# BSPDTester.net
KiCad netlist of a schematic drawn in Altium Designer
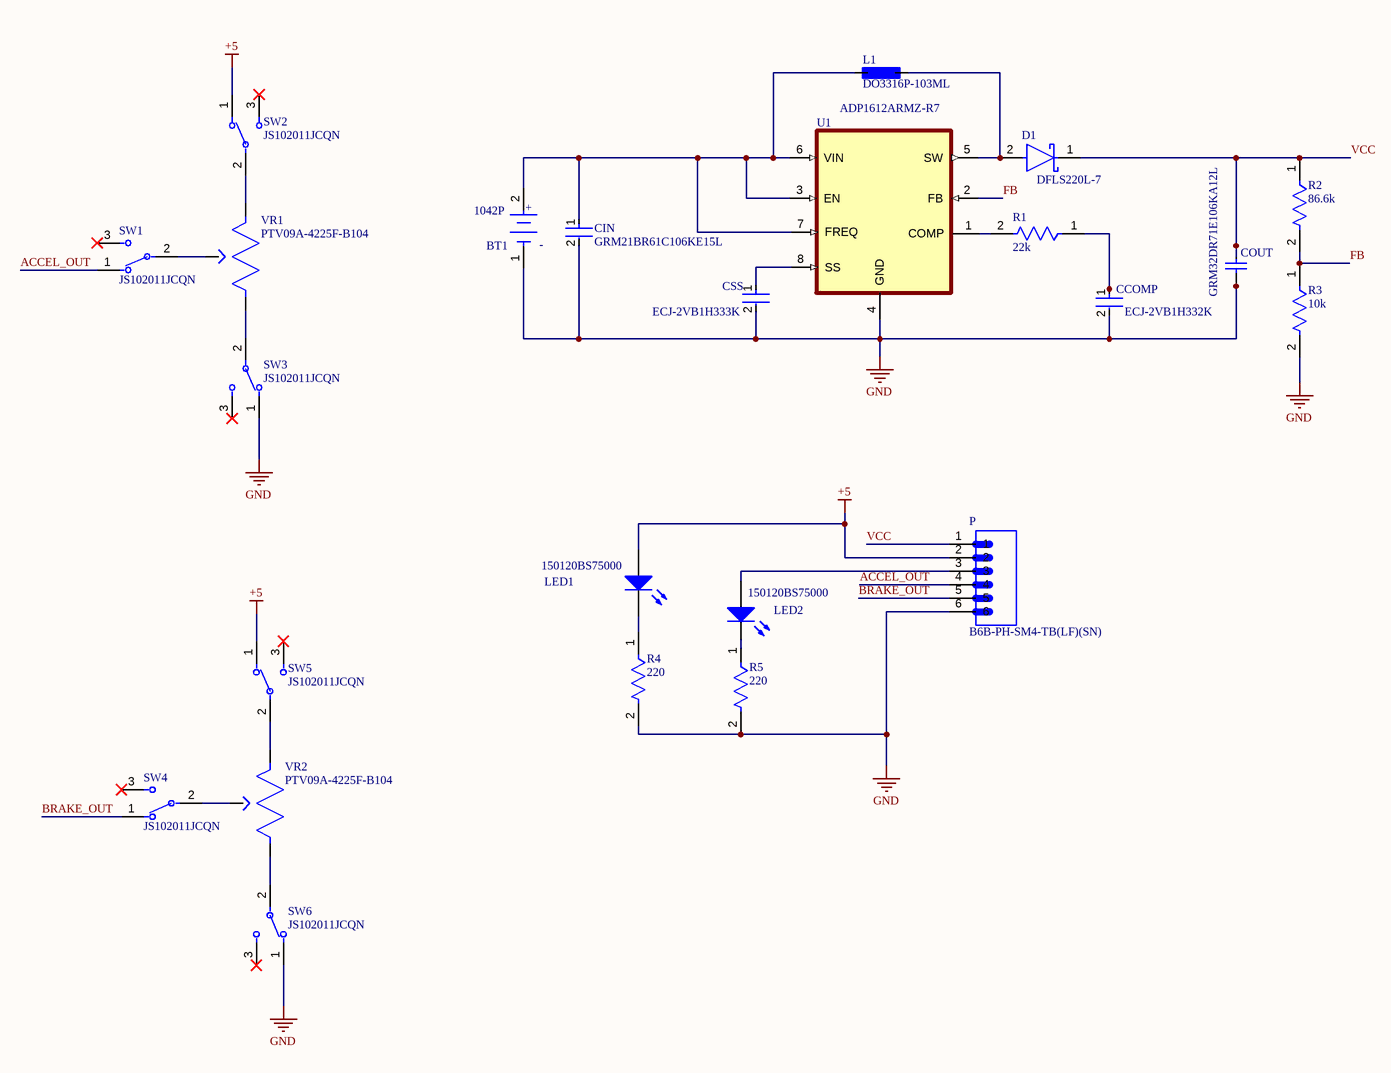
[diagram p0: BSPDTester.SchDoc]

(export (version "E")
  (design (tool "Eeschema 10.0.6"))
  (components
    (comp (ref "BT1")
      (value "1042P")
      (footprint "FP-1042P-MFG")
      (description "BATTERY HOLDER 18650 SMD TAB")
      (libsource (lib "Altium Content Vault") (part "60d3b5b901a8747834971d0eb8cf3fd"))
    )
    (comp (ref "CCOMP")
      (value "ECJ-2VB1H332K")
      (footprint "FP-C0805C-DG-MFG")
      (description "CAP CER 10UF 10V X5R 0805")
      (fields (field (name "TOLERANCE") "10%") (field (name "MANUFACTURER PART NUMBER") "C0805C106K8PACTU"))
      (libsource (lib "Altium Content Vault") (part "11868f565c42a9108669ba33697ecf6"))
    )
    (comp (ref "CIN")
      (value "GRM21BR61C106KE15L")
      (footprint "FP-GRM21B-0_1-IPC_C")
      (description "Chip Multilayer Ceramic Capacitors for General Purpose, 0805, 10uF, X5R, 15%, 10%, 16V")
      (fields (field (name "TOLERANCE") "10%") (field (name "VOLTAGE") "16V"))
      (libsource (lib "Altium Content Vault") (part "b4654b650e69147ec39a6b967a45e02"))
    )
    (comp (ref "COUT")
      (value "GRM32DR71E106KA12L")
      (footprint "CAPC3225X220X30LL30")
      (description "Chip Capacitor, 10 uF, +/- 10%, 25 V, -55 to 125 degC, 1210 (3225 Metric), RoHS, Tape and Reel")
      (fields (field (name "MANUFACTURER") "Murata"))
      (libsource (lib "Altium Content Vault") (part "CAP-NP-2"))
    )
    (comp (ref "CSS")
      (value "ECJ-2VB1H333K")
      (footprint "FP-C0805C-DG-MFG")
      (description "CAP CER 10UF 10V X5R 0805")
      (fields (field (name "TOLERANCE") "10%") (field (name "MANUFACTURER PART NUMBER") "C0805C106K8PACTU"))
      (libsource (lib "Altium Content Vault") (part "11868f565c42a9108669ba33697ecf6"))
    )
    (comp (ref "D1")
      (value "DFLS220L-7")
      (footprint "FP-PowerDI123-MFG")
      (description "DIODE SCHOTTKY 20V 2A POWERDI123")
      (fields
        (field (name "MANUFACTURER") "Diodes Inc.")
        (field (name "OCTOPART") "https://octopart.com/dfls220l-7-diodes+inc.-328575")
      )
      (libsource (lib "Altium Content Vault") (part "1d6ec82d83fb6aee721767c19dac4b9"))
    )
    (comp (ref "L1")
      (value "DO3316P-103ML")
      (footprint "DO3316P")
      (description "<b>COILCRAFT</b>")
      (fields (field (name "MP") "DO3316P") (field (name "MF") "Coilcraft"))
      (libsource (lib "DO3316P") (part "DO3316P"))
    )
    (comp (ref "LED1")
      (value "150120BS75000")
      (footprint "1206_A")
      (description "SMD mono-color Chip LED, WL-SMCW, Blue")
      (fields (field (name "MANUFACTURER") "Wuerth Elektronik"))
      (libsource (lib "Altium Content Vault") (part "WE-LED_K1A2-2"))
    )
    (comp (ref "LED2")
      (value "150120BS75000")
      (footprint "1206_A")
      (description "SMD mono-color Chip LED, WL-SMCW, Blue")
      (fields (field (name "MANUFACTURER") "Wuerth Elektronik"))
      (libsource (lib "Altium Content Vault") (part "WE-LED_K1A2-2"))
    )
    (comp (ref "P")
      (value "B6B-PH-SM4-TB(LF)(SN)")
      (footprint "JST_B6B-PH-SM4-TB(LF)(SN)")
      (description "Connector Header Surface Mount 6 position 0.079 _2.00mm_")
      (fields (field (name "MF") "JST Sales") (field (name "MP") "B6B-PH-SM4-TB_LF__SN_"))
      (libsource (lib "B6B-PH-SM4-TB_LF__SN_") (part "B6B-PH-SM4-TB(LF)(SN)"))
    )
    (comp (ref "R1")
      (value "22k")
      (footprint "FP-CRCW1206-e3-IPC_A")
      (description "RES Thick Film, 22kΩ, 1%, 0.25W, 100ppm/°C, 1206")
      (fields (field (name "TOLERANCE") "1%"))
      (libsource (lib "Altium Content Vault") (part "1029c3af85768c4190bb7ad29bc67b5"))
    )
    (comp (ref "R2")
      (value "86.6k")
      (footprint "FP-CRCW1206-e3-IPC_A")
      (description "RES Thick Film, 22kΩ, 1%, 0.25W, 100ppm/°C, 1206")
      (fields (field (name "TOLERANCE") "1%"))
      (libsource (lib "Altium Content Vault") (part "1029c3af85768c4190bb7ad29bc67b5"))
    )
    (comp (ref "R3")
      (value "10k")
      (footprint "FP-CRCW1206-e3-IPC_A")
      (description "RES Thick Film, 22kΩ, 1%, 0.25W, 100ppm/°C, 1206")
      (fields (field (name "TOLERANCE") "1%"))
      (libsource (lib "Altium Content Vault") (part "1029c3af85768c4190bb7ad29bc67b5"))
    )
    (comp (ref "R4")
      (value "220")
      (footprint "FP-CRCW1206-e3-IPC_A")
      (description "RES Thick Film, 22kΩ, 1%, 0.25W, 100ppm/°C, 1206")
      (fields (field (name "TOLERANCE") "1%"))
      (libsource (lib "Altium Content Vault") (part "1029c3af85768c4190bb7ad29bc67b5"))
    )
    (comp (ref "R5")
      (value "220")
      (footprint "FP-CRCW1206-e3-IPC_A")
      (description "RES Thick Film, 22kΩ, 1%, 0.25W, 100ppm/°C, 1206")
      (fields (field (name "TOLERANCE") "1%"))
      (libsource (lib "Altium Content Vault") (part "1029c3af85768c4190bb7ad29bc67b5"))
    )
    (comp (ref "SW1")
      (value "JS102011JCQN")
      (footprint "FP-JS102011JCQN-MFG")
      (description "SWITCH SLIDE SPDT 300MA 6V")
      (libsource (lib "Altium Content Vault") (part "52c419afdc2a387c7d548259a9aeefb"))
    )
    (comp (ref "SW2")
      (value "JS102011JCQN")
      (footprint "FP-JS102011JCQN-MFG")
      (description "SWITCH SLIDE SPDT 300MA 6V")
      (libsource (lib "Altium Content Vault") (part "52c419afdc2a387c7d548259a9aeefb"))
    )
    (comp (ref "SW3")
      (value "JS102011JCQN")
      (footprint "FP-JS102011JCQN-MFG")
      (description "SWITCH SLIDE SPDT 300MA 6V")
      (libsource (lib "Altium Content Vault") (part "52c419afdc2a387c7d548259a9aeefb"))
    )
    (comp (ref "SW4")
      (value "JS102011JCQN")
      (footprint "FP-JS102011JCQN-MFG")
      (description "SWITCH SLIDE SPDT 300MA 6V")
      (libsource (lib "Altium Content Vault") (part "52c419afdc2a387c7d548259a9aeefb"))
    )
    (comp (ref "SW5")
      (value "JS102011JCQN")
      (footprint "FP-JS102011JCQN-MFG")
      (description "SWITCH SLIDE SPDT 300MA 6V")
      (libsource (lib "Altium Content Vault") (part "52c419afdc2a387c7d548259a9aeefb"))
    )
    (comp (ref "SW6")
      (value "JS102011JCQN")
      (footprint "FP-JS102011JCQN-MFG")
      (description "SWITCH SLIDE SPDT 300MA 6V")
      (libsource (lib "Altium Content Vault") (part "52c419afdc2a387c7d548259a9aeefb"))
    )
    (comp (ref "U1")
      (value "ADP1612ARMZ-R7")
      (footprint "SOIC-08")
      (fields (field (name "MF") "Analog Devices"))
      (libsource (lib "ADP1612ARMZ-R7") (part "ADP1612ARMZ-R7"))
    )
    (comp (ref "VR1")
      (value "PTV09A-4225F-B104")
      (footprint "PTV09")
      (fields (field (name "MF") "Bourns"))
      (libsource (lib "PTV09A-4225F-B104") (part "PTV09A-4225F-B104"))
    )
    (comp (ref "VR2")
      (value "PTV09A-4225F-B104")
      (footprint "PTV09")
      (fields (field (name "MF") "Bourns"))
      (libsource (lib "PTV09A-4225F-B104") (part "PTV09A-4225F-B104"))
    )
  )
  (nets
    (net (code "1") (name "+5") (class "Default")
      (node (ref "LED1") (pin "2") (pinfunction "A_2") (pintype "passive"))
      (node (ref "P") (pin "2") (pinfunction "2_2") (pintype "passive"))
      (node (ref "SW2") (pin "1") (pinfunction "1_1") (pintype "passive"))
      (node (ref "SW5") (pin "1") (pinfunction "1_1") (pintype "passive"))
    )
    (net (code "2") (name "/ACCEL_OUT") (class "Default")
      (node (ref "P") (pin "4") (pinfunction "4_4") (pintype "passive"))
      (node (ref "SW1") (pin "1") (pinfunction "1_1") (pintype "passive"))
    )
    (net (code "3") (name "/BRAKE_OUT") (class "Default")
      (node (ref "P") (pin "5") (pinfunction "5_5") (pintype "passive"))
      (node (ref "SW4") (pin "1") (pinfunction "1_1") (pintype "passive"))
    )
    (net (code "4") (name "/FB") (class "Default")
      (node (ref "R2") (pin "2") (pinfunction "2_2") (pintype "passive"))
      (node (ref "R3") (pin "1") (pinfunction "1_1") (pintype "passive"))
      (node (ref "U1") (pin "2") (pinfunction "FB_2") (pintype "input"))
    )
    (net (code "5") (name "/VCC") (class "Default")
      (node (ref "COUT") (pin "2") (pinfunction "2_2") (pintype "passive"))
      (node (ref "D1") (pin "1") (pinfunction "C_1") (pintype "passive"))
      (node (ref "P") (pin "1") (pinfunction "1_1") (pintype "passive"))
      (node (ref "R2") (pin "1") (pinfunction "1_1") (pintype "passive"))
    )
    (net (code "6") (name "GND") (class "Default")
      (node (ref "BT1") (pin "1") (pinfunction "C_1") (pintype "passive"))
      (node (ref "CCOMP") (pin "2") (pinfunction "2_2") (pintype "passive"))
      (node (ref "CIN") (pin "2") (pinfunction "2_2") (pintype "passive"))
      (node (ref "COUT") (pin "1") (pinfunction "1_1") (pintype "passive"))
      (node (ref "CSS") (pin "2") (pinfunction "2_2") (pintype "passive"))
      (node (ref "P") (pin "6") (pinfunction "6_6") (pintype "passive"))
      (node (ref "R3") (pin "2") (pinfunction "2_2") (pintype "passive"))
      (node (ref "R4") (pin "2") (pinfunction "2_2") (pintype "passive"))
      (node (ref "R5") (pin "2") (pinfunction "2_2") (pintype "passive"))
      (node (ref "SW3") (pin "1") (pinfunction "1_1") (pintype "passive"))
      (node (ref "SW6") (pin "1") (pinfunction "1_1") (pintype "passive"))
      (node (ref "U1") (pin "4") (pinfunction "GND_4") (pintype "passive"))
    )
    (net (code "7") (name "Net-(BT1-A)") (class "Default")
      (node (ref "BT1") (pin "2") (pinfunction "A_2") (pintype "passive"))
      (node (ref "CIN") (pin "1") (pinfunction "1_1") (pintype "passive"))
      (node (ref "L1") (pin "1") (pinfunction "1_1") (pintype "passive"))
      (node (ref "U1") (pin "3") (pinfunction "EN_3") (pintype "input"))
      (node (ref "U1") (pin "6") (pinfunction "VIN_6") (pintype "input"))
      (node (ref "U1") (pin "7") (pinfunction "FREQ_7") (pintype "input"))
    )
    (net (code "8") (name "Net-(CCOMP-Pad1)") (class "Default")
      (node (ref "CCOMP") (pin "1") (pinfunction "1_1") (pintype "passive"))
      (node (ref "R1") (pin "1") (pinfunction "1_1") (pintype "passive"))
    )
    (net (code "9") (name "Net-(D1-A)") (class "Default")
      (node (ref "D1") (pin "2") (pinfunction "A_2") (pintype "passive"))
      (node (ref "L1") (pin "2") (pinfunction "2_2") (pintype "passive"))
      (node (ref "U1") (pin "5") (pinfunction "SW_5") (pintype "output"))
    )
    (net (code "10") (name "Net-(LED1-K)") (class "Default")
      (node (ref "LED1") (pin "1") (pinfunction "K_1") (pintype "passive"))
      (node (ref "R4") (pin "1") (pinfunction "1_1") (pintype "passive"))
    )
    (net (code "11") (name "Net-(LED2-A)") (class "Default")
      (node (ref "LED2") (pin "2") (pinfunction "A_2") (pintype "passive"))
      (node (ref "P") (pin "3") (pinfunction "3_3") (pintype "passive"))
    )
    (net (code "12") (name "Net-(LED2-K)") (class "Default")
      (node (ref "LED2") (pin "1") (pinfunction "K_1") (pintype "passive"))
      (node (ref "R5") (pin "1") (pinfunction "1_1") (pintype "passive"))
    )
    (net (code "13") (name "Net-(SW1-Pad2)") (class "Default")
      (node (ref "SW1") (pin "2") (pinfunction "2_2") (pintype "passive"))
      (node (ref "VR1") (pin "2") (pinfunction "2_2") (pintype "bidirectional"))
    )
    (net (code "14") (name "Net-(SW2-Pad2)") (class "Default")
      (node (ref "SW2") (pin "2") (pinfunction "2_2") (pintype "passive"))
      (node (ref "VR1") (pin "1") (pinfunction "1_1") (pintype "bidirectional"))
    )
    (net (code "15") (name "Net-(SW3-Pad2)") (class "Default")
      (node (ref "SW3") (pin "2") (pinfunction "2_2") (pintype "passive"))
      (node (ref "VR1") (pin "3") (pinfunction "3_3") (pintype "bidirectional"))
    )
    (net (code "16") (name "Net-(SW4-Pad2)") (class "Default")
      (node (ref "SW4") (pin "2") (pinfunction "2_2") (pintype "passive"))
      (node (ref "VR2") (pin "2") (pinfunction "2_2") (pintype "bidirectional"))
    )
    (net (code "17") (name "Net-(SW5-Pad2)") (class "Default")
      (node (ref "SW5") (pin "2") (pinfunction "2_2") (pintype "passive"))
      (node (ref "VR2") (pin "1") (pinfunction "1_1") (pintype "bidirectional"))
    )
    (net (code "18") (name "Net-(SW6-Pad2)") (class "Default")
      (node (ref "SW6") (pin "2") (pinfunction "2_2") (pintype "passive"))
      (node (ref "VR2") (pin "3") (pinfunction "3_3") (pintype "bidirectional"))
    )
    (net (code "19") (name "Net-(U1-COMP)") (class "Default")
      (node (ref "R1") (pin "2") (pinfunction "2_2") (pintype "passive"))
      (node (ref "U1") (pin "1") (pinfunction "COMP_1") (pintype "passive"))
    )
    (net (code "20") (name "Net-(U1-SS)") (class "Default")
      (node (ref "CSS") (pin "1") (pinfunction "1_1") (pintype "passive"))
      (node (ref "U1") (pin "8") (pinfunction "SS_8") (pintype "input"))
    )
    (net (code "21") (name "unconnected-(SW1-Pad3)") (class "Default")
      (node (ref "SW1") (pin "3") (pinfunction "3_3") (pintype "passive+no_connect"))
    )
    (net (code "22") (name "unconnected-(SW2-Pad3)") (class "Default")
      (node (ref "SW2") (pin "3") (pinfunction "3_3") (pintype "passive+no_connect"))
    )
    (net (code "23") (name "unconnected-(SW3-Pad3)") (class "Default")
      (node (ref "SW3") (pin "3") (pinfunction "3_3") (pintype "passive+no_connect"))
    )
    (net (code "24") (name "unconnected-(SW4-Pad3)") (class "Default")
      (node (ref "SW4") (pin "3") (pinfunction "3_3") (pintype "passive+no_connect"))
    )
    (net (code "25") (name "unconnected-(SW5-Pad3)") (class "Default")
      (node (ref "SW5") (pin "3") (pinfunction "3_3") (pintype "passive+no_connect"))
    )
    (net (code "26") (name "unconnected-(SW6-Pad3)") (class "Default")
      (node (ref "SW6") (pin "3") (pinfunction "3_3") (pintype "passive+no_connect"))
    )
  )
)
